# hw-proto04.net
KiCad netlist of a schematic drawn in EAGLE
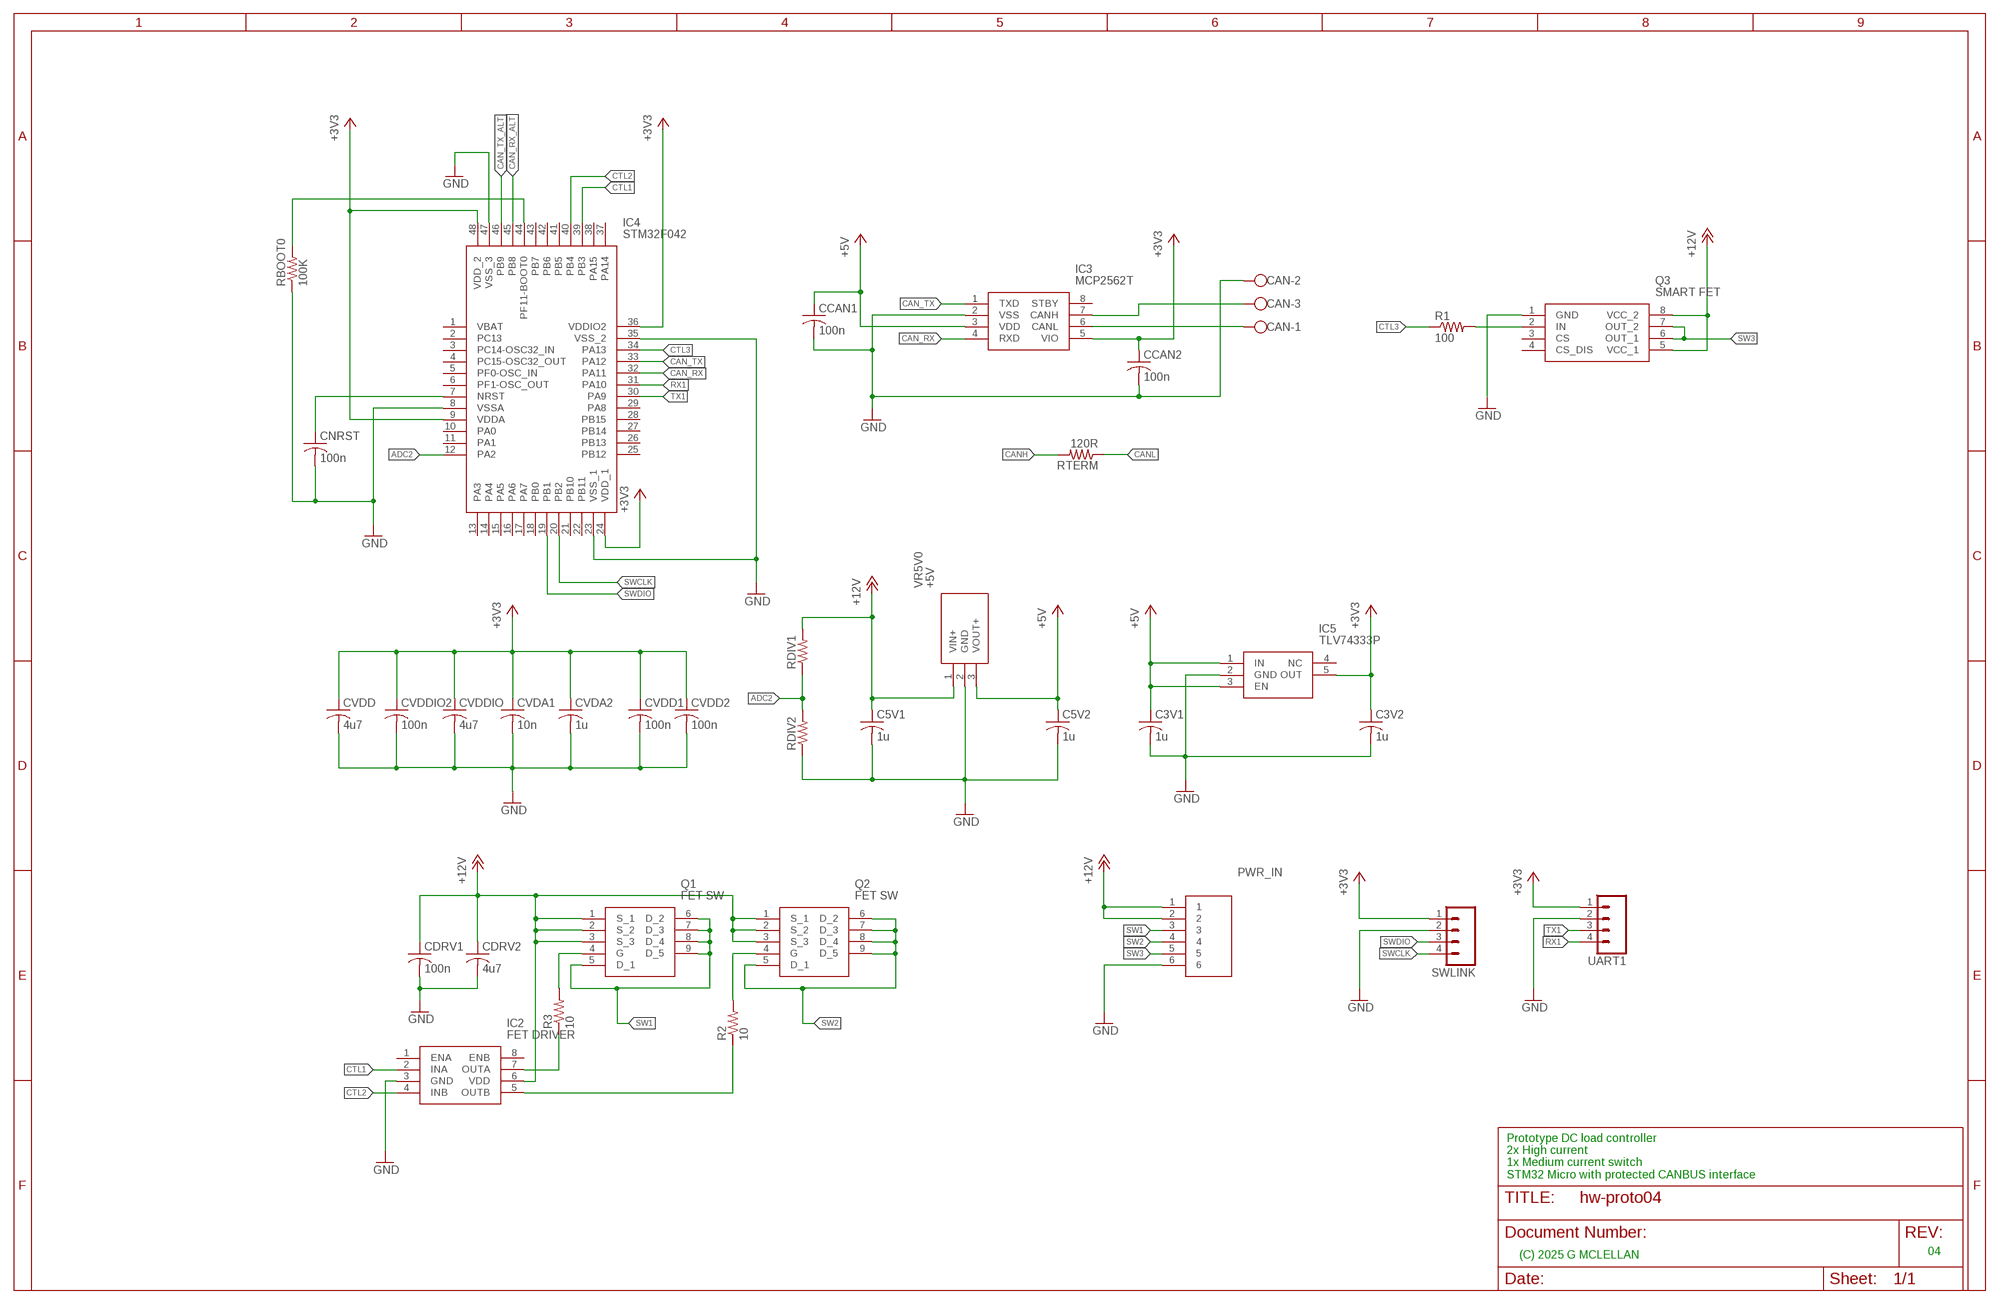
[diagram p0: schematic, sheet 1]

(export (version "E")
  (design (tool "Eeschema 10.0.6"))
  (components
    (comp (ref "C3V1")
      (value "1u")
      (footprint "eagle-import:C0603K")
      (libsource (lib "eagle-import") (part "C-USC0603K"))
    )
    (comp (ref "C3V2")
      (value "1u")
      (footprint "eagle-import:C0603K")
      (libsource (lib "eagle-import") (part "C-USC0603K"))
    )
    (comp (ref "C5V1")
      (value "1u")
      (footprint "eagle-import:C0603K")
      (libsource (lib "eagle-import") (part "C-USC0603K"))
    )
    (comp (ref "C5V2")
      (value "1u")
      (footprint "eagle-import:C0603K")
      (libsource (lib "eagle-import") (part "C-USC0603K"))
    )
    (comp (ref "CAN")
      (value "W237-103")
      (footprint "eagle-import:W237-103")
      (fields (field (name "MPN") "237-103"))
      (libsource (lib "eagle-import") (part "W237-103"))
    )
    (comp (ref "CCAN1")
      (value "100n")
      (footprint "eagle-import:C0603K")
      (libsource (lib "eagle-import") (part "C-USC0603K"))
    )
    (comp (ref "CCAN2")
      (value "100n")
      (footprint "eagle-import:C0603K")
      (libsource (lib "eagle-import") (part "C-USC0603K"))
    )
    (comp (ref "CDRV1")
      (value "100n")
      (footprint "eagle-import:C0603K")
      (libsource (lib "eagle-import") (part "C-USC0603K"))
    )
    (comp (ref "CDRV2")
      (value "4u7")
      (footprint "eagle-import:C0805K")
      (libsource (lib "eagle-import") (part "C-USC0805K"))
    )
    (comp (ref "CNRST")
      (value "100n")
      (footprint "eagle-import:C0603K")
      (libsource (lib "eagle-import") (part "C-USC0603K"))
    )
    (comp (ref "CVDA1")
      (value "10n")
      (footprint "eagle-import:C0603K")
      (libsource (lib "eagle-import") (part "C-USC0603K"))
    )
    (comp (ref "CVDA2")
      (value "1u")
      (footprint "eagle-import:C0603K")
      (libsource (lib "eagle-import") (part "C-USC0603K"))
    )
    (comp (ref "CVDD")
      (value "4u7")
      (footprint "eagle-import:C0603K")
      (libsource (lib "eagle-import") (part "C-USC0603K"))
    )
    (comp (ref "CVDD1")
      (value "100n")
      (footprint "eagle-import:C0603K")
      (libsource (lib "eagle-import") (part "C-USC0603K"))
    )
    (comp (ref "CVDD2")
      (value "100n")
      (footprint "eagle-import:C0603K")
      (libsource (lib "eagle-import") (part "C-USC0603K"))
    )
    (comp (ref "CVDDIO")
      (value "4u7")
      (footprint "eagle-import:C0603K")
      (libsource (lib "eagle-import") (part "C-USC0603K"))
    )
    (comp (ref "CVDDIO2")
      (value "100n")
      (footprint "eagle-import:C0603K")
      (libsource (lib "eagle-import") (part "C-USC0603K"))
    )
    (comp (ref "IC2")
      (value "FET DRIVER")
      (footprint "eagle-import:SOIC127P600X175-8N")
      (fields
        (field (name "MANUFACTURER_PART_NUMBER") "UCC27523DR")
        (field (name "MOUSER_PART_NUMBER") "595-UCC27523DR")
      )
      (libsource (lib "eagle-import") (part "UCC27523DR"))
    )
    (comp (ref "IC3")
      (value "MCP2562T")
      (footprint "eagle-import:SOIC127P600X175-8N")
      (fields
        (field (name "MANUFACTURER_PART_NUMBER") "MCP2562T-H/SN")
        (field (name "MOUSER_PART_NUMBER") "579-MCP2562T-H/SN")
      )
      (libsource (lib "eagle-import") (part "MCP2562T-H_SN"))
    )
    (comp (ref "IC4")
      (value "STM32F042")
      (footprint "eagle-import:QFP50P900X900X160-48N")
      (fields
        (field (name "MANUFACTURER_PART_NUMBER") "STM32F042C6T7")
        (field (name "MOUSER_PART_NUMBER") "511-STM32F042C6T7")
      )
      (libsource (lib "eagle-import") (part "STM32F042C6T7"))
    )
    (comp (ref "IC5")
      (value "TLV74333P")
      (footprint "eagle-import:SOT95P280X145-5N")
      (fields
        (field (name "MANUFACTURER_PART_NUMBER") "TLV74333PDBVR")
        (field (name "MOUSER_PART_NUMBER") "595-TLV74333PDBVR")
      )
      (libsource (lib "eagle-import") (part "TLV74333PDBVR"))
    )
    (comp (ref "PWR_IN")
      (value "4DB-P108-06")
      (footprint "eagle-import:4DBP10806")
      (libsource (lib "eagle-import") (part "4DB-P108-06"))
    )
    (comp (ref "Q1")
      (value "FET SW")
      (footprint "eagle-import:SQJ147ELPT1_GE3")
      (fields
        (field (name "MANUFACTURER_PART_NUMBER") "SQJ147ELP-T1_GE3")
        (field (name "MOUSER_PART_NUMBER") "78-SQJ147ELP-T1_GE3")
      )
      (libsource (lib "eagle-import") (part "SQJ147ELP-T1_GE3"))
    )
    (comp (ref "Q2")
      (value "FET SW")
      (footprint "eagle-import:SQJ147ELPT1_GE3")
      (fields
        (field (name "MANUFACTURER_PART_NUMBER") "SQJ147ELP-T1_GE3")
        (field (name "MOUSER_PART_NUMBER") "78-SQJ147ELP-T1_GE3")
      )
      (libsource (lib "eagle-import") (part "SQJ147ELP-T1_GE3"))
    )
    (comp (ref "Q3")
      (value "SMART FET")
      (footprint "eagle-import:SOIC127P600X175-8N")
      (fields
        (field (name "MANUFACTURER_PART_NUMBER") "VN5E160MSTR-E")
        (field (name "MOUSER_PART_NUMBER") "511-VN5E160MSTR-E")
      )
      (libsource (lib "eagle-import") (part "VN5E160MSTR-E"))
    )
    (comp (ref "R1")
      (value "100")
      (footprint "eagle-import:0204_7")
      (libsource (lib "eagle-import") (part "R-US_0204/7"))
    )
    (comp (ref "R2")
      (value "10")
      (footprint "eagle-import:0204_7")
      (libsource (lib "eagle-import") (part "R-US_0204/7"))
    )
    (comp (ref "R3")
      (value "10")
      (footprint "eagle-import:0204_7")
      (libsource (lib "eagle-import") (part "R-US_0204/7"))
    )
    (comp (ref "RBOOT0")
      (value "100K")
      (footprint "eagle-import:R0603")
      (libsource (lib "eagle-import") (part "R-US_R0603"))
    )
    (comp (ref "RDIV1")
      (value "R-US_R0805")
      (footprint "eagle-import:R0805")
      (libsource (lib "eagle-import") (part "R-US_R0805"))
    )
    (comp (ref "RDIV2")
      (value "R-US_R0805")
      (footprint "eagle-import:R0805")
      (libsource (lib "eagle-import") (part "R-US_R0805"))
    )
    (comp (ref "RTERM")
      (value "120R")
      (footprint "eagle-import:R0805")
      (libsource (lib "eagle-import") (part "R-US_R0805"))
    )
    (comp (ref "SWLINK")
      (value "M04LOCK")
      (footprint "eagle-import:1X04_LOCK")
      (libsource (lib "eagle-import") (part "M04LOCK"))
    )
    (comp (ref "UART1")
      (value "M04LOCK")
      (footprint "eagle-import:1X04_LOCK")
      (libsource (lib "eagle-import") (part "M04LOCK"))
    )
    (comp (ref "VR5V0")
      (value "+5V")
      (footprint "eagle-import:TSR-1-2433")
      (fields
        (field (name "MANUFACTURER_PART_NUMBER") "TSR 1-2433E")
        (field (name "MOUSER_PART_NUMBER") "495-TSR1-2433E")
      )
      (libsource (lib "eagle-import") (part "TSR_1-2433E"))
    )
  )
  (nets
    (net (code "1") (name "+3V3") (class "Default")
      (node (ref "C3V2") (pin "1") (pinfunction "1_1") (pintype "passive"))
      (node (ref "CCAN2") (pin "1") (pinfunction "1_1") (pintype "passive"))
      (node (ref "CVDA1") (pin "1") (pinfunction "1_1") (pintype "passive"))
      (node (ref "CVDA2") (pin "1") (pinfunction "1_1") (pintype "passive"))
      (node (ref "CVDD") (pin "1") (pinfunction "1_1") (pintype "passive"))
      (node (ref "CVDD1") (pin "1") (pinfunction "1_1") (pintype "passive"))
      (node (ref "CVDD2") (pin "1") (pinfunction "1_1") (pintype "passive"))
      (node (ref "CVDDIO") (pin "1") (pinfunction "1_1") (pintype "passive"))
      (node (ref "CVDDIO2") (pin "1") (pinfunction "1_1") (pintype "passive"))
      (node (ref "IC3") (pin "5") (pinfunction "VIO_5") (pintype "bidirectional"))
      (node (ref "IC4") (pin "24") (pinfunction "VDD_1_24") (pintype "bidirectional"))
      (node (ref "IC4") (pin "36") (pinfunction "VDDIO2_36") (pintype "bidirectional"))
      (node (ref "IC4") (pin "48") (pinfunction "VDD_2_48") (pintype "bidirectional"))
      (node (ref "IC4") (pin "9") (pinfunction "VDDA_9") (pintype "bidirectional"))
      (node (ref "IC5") (pin "5") (pinfunction "OUT_5") (pintype "bidirectional"))
      (node (ref "SWLINK") (pin "1") (pinfunction "1_1") (pintype "passive"))
      (node (ref "UART1") (pin "1") (pinfunction "1_1") (pintype "passive"))
    )
    (net (code "2") (name "+5V") (class "Default")
      (node (ref "C3V1") (pin "1") (pinfunction "1_1") (pintype "passive"))
      (node (ref "C5V2") (pin "1") (pinfunction "1_1") (pintype "passive"))
      (node (ref "CCAN1") (pin "1") (pinfunction "1_1") (pintype "passive"))
      (node (ref "IC3") (pin "3") (pinfunction "VDD_3") (pintype "bidirectional"))
      (node (ref "IC5") (pin "1") (pinfunction "IN_1") (pintype "bidirectional"))
      (node (ref "IC5") (pin "3") (pinfunction "EN_3") (pintype "bidirectional"))
      (node (ref "VR5V0") (pin "3") (pinfunction "VOUT+_3") (pintype "output"))
    )
    (net (code "3") (name "+12V") (class "Default")
      (node (ref "C5V1") (pin "1") (pinfunction "1_1") (pintype "passive"))
      (node (ref "CDRV1") (pin "1") (pinfunction "1_1") (pintype "passive"))
      (node (ref "CDRV2") (pin "1") (pinfunction "1_1") (pintype "passive"))
      (node (ref "IC2") (pin "6") (pinfunction "VDD_6") (pintype "bidirectional"))
      (node (ref "PWR_IN") (pin "1") (pinfunction "1_1") (pintype "bidirectional"))
      (node (ref "PWR_IN") (pin "2") (pinfunction "2_2") (pintype "bidirectional"))
      (node (ref "Q1") (pin "1") (pinfunction "S_1_1") (pintype "bidirectional"))
      (node (ref "Q1") (pin "2") (pinfunction "S_2_2") (pintype "bidirectional"))
      (node (ref "Q1") (pin "3") (pinfunction "S_3_3") (pintype "bidirectional"))
      (node (ref "Q2") (pin "1") (pinfunction "S_1_1") (pintype "bidirectional"))
      (node (ref "Q2") (pin "2") (pinfunction "S_2_2") (pintype "bidirectional"))
      (node (ref "Q2") (pin "3") (pinfunction "S_3_3") (pintype "bidirectional"))
      (node (ref "Q3") (pin "5") (pinfunction "VCC_1_5") (pintype "bidirectional"))
      (node (ref "Q3") (pin "8") (pinfunction "VCC_2_8") (pintype "bidirectional"))
      (node (ref "RDIV1") (pin "2") (pinfunction "2_2") (pintype "passive"))
      (node (ref "VR5V0") (pin "1") (pinfunction "VIN+_1") (pintype "input"))
    )
    (net (code "4") (name "ADC2") (class "Default")
      (node (ref "IC4") (pin "12") (pinfunction "PA2_12") (pintype "bidirectional"))
      (node (ref "RDIV1") (pin "1") (pinfunction "1_1") (pintype "passive"))
      (node (ref "RDIV2") (pin "2") (pinfunction "2_2") (pintype "passive"))
    )
    (net (code "5") (name "CANH") (class "Default")
      (node (ref "CAN") (pin "3") (pinfunction "KL_3") (pintype "passive"))
      (node (ref "IC3") (pin "7") (pinfunction "CANH_7") (pintype "bidirectional"))
      (node (ref "RTERM") (pin "2") (pinfunction "2_2") (pintype "passive"))
    )
    (net (code "6") (name "CANL") (class "Default")
      (node (ref "CAN") (pin "1") (pinfunction "KL_1") (pintype "passive"))
      (node (ref "IC3") (pin "6") (pinfunction "CANL_6") (pintype "bidirectional"))
      (node (ref "RTERM") (pin "1") (pinfunction "1_1") (pintype "passive"))
    )
    (net (code "7") (name "CAN_RX") (class "Default")
      (node (ref "IC3") (pin "4") (pinfunction "RXD_4") (pintype "bidirectional"))
      (node (ref "IC4") (pin "32") (pinfunction "PA11_32") (pintype "bidirectional"))
    )
    (net (code "8") (name "CAN_RX_ALT") (class "Default")
      (node (ref "IC4") (pin "45") (pinfunction "PB8_45") (pintype "bidirectional"))
    )
    (net (code "9") (name "CAN_TX") (class "Default")
      (node (ref "IC3") (pin "1") (pinfunction "TXD_1") (pintype "bidirectional"))
      (node (ref "IC4") (pin "33") (pinfunction "PA12_33") (pintype "bidirectional"))
    )
    (net (code "10") (name "CAN_TX_ALT") (class "Default")
      (node (ref "IC4") (pin "46") (pinfunction "PB9_46") (pintype "bidirectional"))
    )
    (net (code "11") (name "CTL1") (class "Default")
      (node (ref "IC2") (pin "2") (pinfunction "INA_2") (pintype "bidirectional"))
      (node (ref "IC4") (pin "39") (pinfunction "PB3_39") (pintype "bidirectional"))
    )
    (net (code "12") (name "CTL2") (class "Default")
      (node (ref "IC2") (pin "4") (pinfunction "INB_4") (pintype "bidirectional"))
      (node (ref "IC4") (pin "40") (pinfunction "PB4_40") (pintype "bidirectional"))
    )
    (net (code "13") (name "CTL3") (class "Default")
      (node (ref "IC4") (pin "34") (pinfunction "PA13_34") (pintype "bidirectional"))
      (node (ref "R1") (pin "1") (pinfunction "1_1") (pintype "passive"))
    )
    (net (code "14") (name "GND") (class "Default")
      (node (ref "C3V1") (pin "2") (pinfunction "2_2") (pintype "passive"))
      (node (ref "C3V2") (pin "2") (pinfunction "2_2") (pintype "passive"))
      (node (ref "C5V1") (pin "2") (pinfunction "2_2") (pintype "passive"))
      (node (ref "C5V2") (pin "2") (pinfunction "2_2") (pintype "passive"))
      (node (ref "CAN") (pin "2") (pinfunction "KL_2") (pintype "passive"))
      (node (ref "CCAN1") (pin "2") (pinfunction "2_2") (pintype "passive"))
      (node (ref "CCAN2") (pin "2") (pinfunction "2_2") (pintype "passive"))
      (node (ref "CDRV1") (pin "2") (pinfunction "2_2") (pintype "passive"))
      (node (ref "CDRV2") (pin "2") (pinfunction "2_2") (pintype "passive"))
      (node (ref "CNRST") (pin "2") (pinfunction "2_2") (pintype "passive"))
      (node (ref "CVDA1") (pin "2") (pinfunction "2_2") (pintype "passive"))
      (node (ref "CVDA2") (pin "2") (pinfunction "2_2") (pintype "passive"))
      (node (ref "CVDD") (pin "2") (pinfunction "2_2") (pintype "passive"))
      (node (ref "CVDD1") (pin "2") (pinfunction "2_2") (pintype "passive"))
      (node (ref "CVDD2") (pin "2") (pinfunction "2_2") (pintype "passive"))
      (node (ref "CVDDIO") (pin "2") (pinfunction "2_2") (pintype "passive"))
      (node (ref "CVDDIO2") (pin "2") (pinfunction "2_2") (pintype "passive"))
      (node (ref "IC2") (pin "3") (pinfunction "GND_3") (pintype "bidirectional"))
      (node (ref "IC3") (pin "2") (pinfunction "VSS_2") (pintype "bidirectional"))
      (node (ref "IC4") (pin "23") (pinfunction "VSS_1_23") (pintype "bidirectional"))
      (node (ref "IC4") (pin "35") (pinfunction "VSS_2_35") (pintype "bidirectional"))
      (node (ref "IC4") (pin "47") (pinfunction "VSS_3_47") (pintype "bidirectional"))
      (node (ref "IC4") (pin "8") (pinfunction "VSSA_8") (pintype "bidirectional"))
      (node (ref "IC5") (pin "2") (pinfunction "GND_2") (pintype "bidirectional"))
      (node (ref "PWR_IN") (pin "6") (pinfunction "6_6") (pintype "bidirectional"))
      (node (ref "Q3") (pin "1") (pinfunction "GND_1") (pintype "bidirectional"))
      (node (ref "RBOOT0") (pin "1") (pinfunction "1_1") (pintype "passive"))
      (node (ref "RDIV2") (pin "1") (pinfunction "1_1") (pintype "passive"))
      (node (ref "SWLINK") (pin "2") (pinfunction "2_2") (pintype "passive"))
      (node (ref "UART1") (pin "2") (pinfunction "2_2") (pintype "passive"))
      (node (ref "VR5V0") (pin "2") (pinfunction "GND_2") (pintype "power_in"))
    )
    (net (code "15") (name "Net-(IC2-OUTA)") (class "Default")
      (node (ref "IC2") (pin "7") (pinfunction "OUTA_7") (pintype "bidirectional"))
      (node (ref "R3") (pin "1") (pinfunction "1_1") (pintype "passive"))
    )
    (net (code "16") (name "Net-(IC2-OUTB)") (class "Default")
      (node (ref "IC2") (pin "5") (pinfunction "OUTB_5") (pintype "bidirectional"))
      (node (ref "R2") (pin "1") (pinfunction "1_1") (pintype "passive"))
    )
    (net (code "17") (name "Net-(IC4-NRST)") (class "Default")
      (node (ref "CNRST") (pin "1") (pinfunction "1_1") (pintype "passive"))
      (node (ref "IC4") (pin "7") (pinfunction "NRST_7") (pintype "bidirectional"))
    )
    (net (code "18") (name "Net-(IC4-PF11-BOOT0)") (class "Default")
      (node (ref "IC4") (pin "44") (pinfunction "PF11-BOOT0_44") (pintype "bidirectional"))
      (node (ref "RBOOT0") (pin "2") (pinfunction "2_2") (pintype "passive"))
    )
    (net (code "19") (name "Net-(Q1-G)") (class "Default")
      (node (ref "Q1") (pin "4") (pinfunction "G_4") (pintype "bidirectional"))
      (node (ref "R3") (pin "2") (pinfunction "2_2") (pintype "passive"))
    )
    (net (code "20") (name "Net-(Q2-G)") (class "Default")
      (node (ref "Q2") (pin "4") (pinfunction "G_4") (pintype "bidirectional"))
      (node (ref "R2") (pin "2") (pinfunction "2_2") (pintype "passive"))
    )
    (net (code "21") (name "Net-(Q3-IN)") (class "Default")
      (node (ref "Q3") (pin "2") (pinfunction "IN_2") (pintype "bidirectional"))
      (node (ref "R1") (pin "2") (pinfunction "2_2") (pintype "passive"))
    )
    (net (code "22") (name "RX1") (class "Default")
      (node (ref "IC4") (pin "31") (pinfunction "PA10_31") (pintype "bidirectional"))
      (node (ref "UART1") (pin "4") (pinfunction "4_4") (pintype "passive"))
    )
    (net (code "23") (name "SW1") (class "Default")
      (node (ref "PWR_IN") (pin "3") (pinfunction "3_3") (pintype "bidirectional"))
      (node (ref "Q1") (pin "5") (pinfunction "D_1_5") (pintype "bidirectional"))
      (node (ref "Q1") (pin "6") (pinfunction "D_2_6") (pintype "bidirectional"))
      (node (ref "Q1") (pin "7") (pinfunction "D_3_7") (pintype "bidirectional"))
      (node (ref "Q1") (pin "8") (pinfunction "D_4_8") (pintype "bidirectional"))
      (node (ref "Q1") (pin "9") (pinfunction "D_5_9") (pintype "bidirectional"))
    )
    (net (code "24") (name "SW2") (class "Default")
      (node (ref "PWR_IN") (pin "4") (pinfunction "4_4") (pintype "bidirectional"))
      (node (ref "Q2") (pin "5") (pinfunction "D_1_5") (pintype "bidirectional"))
      (node (ref "Q2") (pin "6") (pinfunction "D_2_6") (pintype "bidirectional"))
      (node (ref "Q2") (pin "7") (pinfunction "D_3_7") (pintype "bidirectional"))
      (node (ref "Q2") (pin "8") (pinfunction "D_4_8") (pintype "bidirectional"))
      (node (ref "Q2") (pin "9") (pinfunction "D_5_9") (pintype "bidirectional"))
    )
    (net (code "25") (name "SW3") (class "Default")
      (node (ref "PWR_IN") (pin "5") (pinfunction "5_5") (pintype "bidirectional"))
      (node (ref "Q3") (pin "6") (pinfunction "OUT_1_6") (pintype "bidirectional"))
      (node (ref "Q3") (pin "7") (pinfunction "OUT_2_7") (pintype "bidirectional"))
    )
    (net (code "26") (name "SWCLK") (class "Default")
      (node (ref "IC4") (pin "20") (pinfunction "PB2_20") (pintype "bidirectional"))
      (node (ref "SWLINK") (pin "4") (pinfunction "4_4") (pintype "passive"))
    )
    (net (code "27") (name "SWDIO") (class "Default")
      (node (ref "IC4") (pin "19") (pinfunction "PB1_19") (pintype "bidirectional"))
      (node (ref "SWLINK") (pin "3") (pinfunction "3_3") (pintype "passive"))
    )
    (net (code "28") (name "TX1") (class "Default")
      (node (ref "IC4") (pin "30") (pinfunction "PA9_30") (pintype "bidirectional"))
      (node (ref "UART1") (pin "3") (pinfunction "3_3") (pintype "passive"))
    )
    (net (code "29") (name "unconnected-(IC2-ENA-Pad1)") (class "Default")
      (node (ref "IC2") (pin "1") (pinfunction "ENA_1") (pintype "bidirectional"))
    )
    (net (code "30") (name "unconnected-(IC2-ENB-Pad8)") (class "Default")
      (node (ref "IC2") (pin "8") (pinfunction "ENB_8") (pintype "bidirectional"))
    )
    (net (code "31") (name "unconnected-(IC3-STBY-Pad8)") (class "Default")
      (node (ref "IC3") (pin "8") (pinfunction "STBY_8") (pintype "bidirectional"))
    )
    (net (code "32") (name "unconnected-(IC4-PA0-Pad10)") (class "Default")
      (node (ref "IC4") (pin "10") (pinfunction "PA0_10") (pintype "bidirectional"))
    )
    (net (code "33") (name "unconnected-(IC4-PA1-Pad11)") (class "Default")
      (node (ref "IC4") (pin "11") (pinfunction "PA1_11") (pintype "bidirectional"))
    )
    (net (code "34") (name "unconnected-(IC4-PA3-Pad13)") (class "Default")
      (node (ref "IC4") (pin "13") (pinfunction "PA3_13") (pintype "bidirectional"))
    )
    (net (code "35") (name "unconnected-(IC4-PA4-Pad14)") (class "Default")
      (node (ref "IC4") (pin "14") (pinfunction "PA4_14") (pintype "bidirectional"))
    )
    (net (code "36") (name "unconnected-(IC4-PA5-Pad15)") (class "Default")
      (node (ref "IC4") (pin "15") (pinfunction "PA5_15") (pintype "bidirectional"))
    )
    (net (code "37") (name "unconnected-(IC4-PA6-Pad16)") (class "Default")
      (node (ref "IC4") (pin "16") (pinfunction "PA6_16") (pintype "bidirectional"))
    )
    (net (code "38") (name "unconnected-(IC4-PA7-Pad17)") (class "Default")
      (node (ref "IC4") (pin "17") (pinfunction "PA7_17") (pintype "bidirectional"))
    )
    (net (code "39") (name "unconnected-(IC4-PA8-Pad29)") (class "Default")
      (node (ref "IC4") (pin "29") (pinfunction "PA8_29") (pintype "bidirectional"))
    )
    (net (code "40") (name "unconnected-(IC4-PA14-Pad37)") (class "Default")
      (node (ref "IC4") (pin "37") (pinfunction "PA14_37") (pintype "bidirectional"))
    )
    (net (code "41") (name "unconnected-(IC4-PA15-Pad38)") (class "Default")
      (node (ref "IC4") (pin "38") (pinfunction "PA15_38") (pintype "bidirectional"))
    )
    (net (code "42") (name "unconnected-(IC4-PB0-Pad18)") (class "Default")
      (node (ref "IC4") (pin "18") (pinfunction "PB0_18") (pintype "bidirectional"))
    )
    (net (code "43") (name "unconnected-(IC4-PB5-Pad41)") (class "Default")
      (node (ref "IC4") (pin "41") (pinfunction "PB5_41") (pintype "bidirectional"))
    )
    (net (code "44") (name "unconnected-(IC4-PB6-Pad42)") (class "Default")
      (node (ref "IC4") (pin "42") (pinfunction "PB6_42") (pintype "bidirectional"))
    )
    (net (code "45") (name "unconnected-(IC4-PB7-Pad43)") (class "Default")
      (node (ref "IC4") (pin "43") (pinfunction "PB7_43") (pintype "bidirectional"))
    )
    (net (code "46") (name "unconnected-(IC4-PB10-Pad21)") (class "Default")
      (node (ref "IC4") (pin "21") (pinfunction "PB10_21") (pintype "bidirectional"))
    )
    (net (code "47") (name "unconnected-(IC4-PB11-Pad22)") (class "Default")
      (node (ref "IC4") (pin "22") (pinfunction "PB11_22") (pintype "bidirectional"))
    )
    (net (code "48") (name "unconnected-(IC4-PB12-Pad25)") (class "Default")
      (node (ref "IC4") (pin "25") (pinfunction "PB12_25") (pintype "bidirectional"))
    )
    (net (code "49") (name "unconnected-(IC4-PB13-Pad26)") (class "Default")
      (node (ref "IC4") (pin "26") (pinfunction "PB13_26") (pintype "bidirectional"))
    )
    (net (code "50") (name "unconnected-(IC4-PB14-Pad27)") (class "Default")
      (node (ref "IC4") (pin "27") (pinfunction "PB14_27") (pintype "bidirectional"))
    )
    (net (code "51") (name "unconnected-(IC4-PB15-Pad28)") (class "Default")
      (node (ref "IC4") (pin "28") (pinfunction "PB15_28") (pintype "bidirectional"))
    )
    (net (code "52") (name "unconnected-(IC4-PC13-Pad2)") (class "Default")
      (node (ref "IC4") (pin "2") (pinfunction "PC13_2") (pintype "bidirectional"))
    )
    (net (code "53") (name "unconnected-(IC4-PC14-OSC32_IN-Pad3)") (class "Default")
      (node (ref "IC4") (pin "3") (pinfunction "PC14-OSC32_IN_3") (pintype "bidirectional"))
    )
    (net (code "54") (name "unconnected-(IC4-PC15-OSC32_OUT-Pad4)") (class "Default")
      (node (ref "IC4") (pin "4") (pinfunction "PC15-OSC32_OUT_4") (pintype "bidirectional"))
    )
    (net (code "55") (name "unconnected-(IC4-PF0-OSC_IN-Pad5)") (class "Default")
      (node (ref "IC4") (pin "5") (pinfunction "PF0-OSC_IN_5") (pintype "bidirectional"))
    )
    (net (code "56") (name "unconnected-(IC4-PF1-OSC_OUT-Pad6)") (class "Default")
      (node (ref "IC4") (pin "6") (pinfunction "PF1-OSC_OUT_6") (pintype "bidirectional"))
    )
    (net (code "57") (name "unconnected-(IC4-VBAT-Pad1)") (class "Default")
      (node (ref "IC4") (pin "1") (pinfunction "VBAT_1") (pintype "bidirectional"))
    )
    (net (code "58") (name "unconnected-(IC5-NC-Pad4)") (class "Default")
      (node (ref "IC5") (pin "4") (pinfunction "NC_4") (pintype "no_connect"))
    )
    (net (code "59") (name "unconnected-(Q3-CS-Pad3)") (class "Default")
      (node (ref "Q3") (pin "3") (pinfunction "CS_3") (pintype "bidirectional"))
    )
    (net (code "60") (name "unconnected-(Q3-CS_DIS-Pad4)") (class "Default")
      (node (ref "Q3") (pin "4") (pinfunction "CS_DIS_4") (pintype "bidirectional"))
    )
  )
)
